# CONNECTOR_BUS.net
KiCad netlist of a schematic drawn in Altium Designer
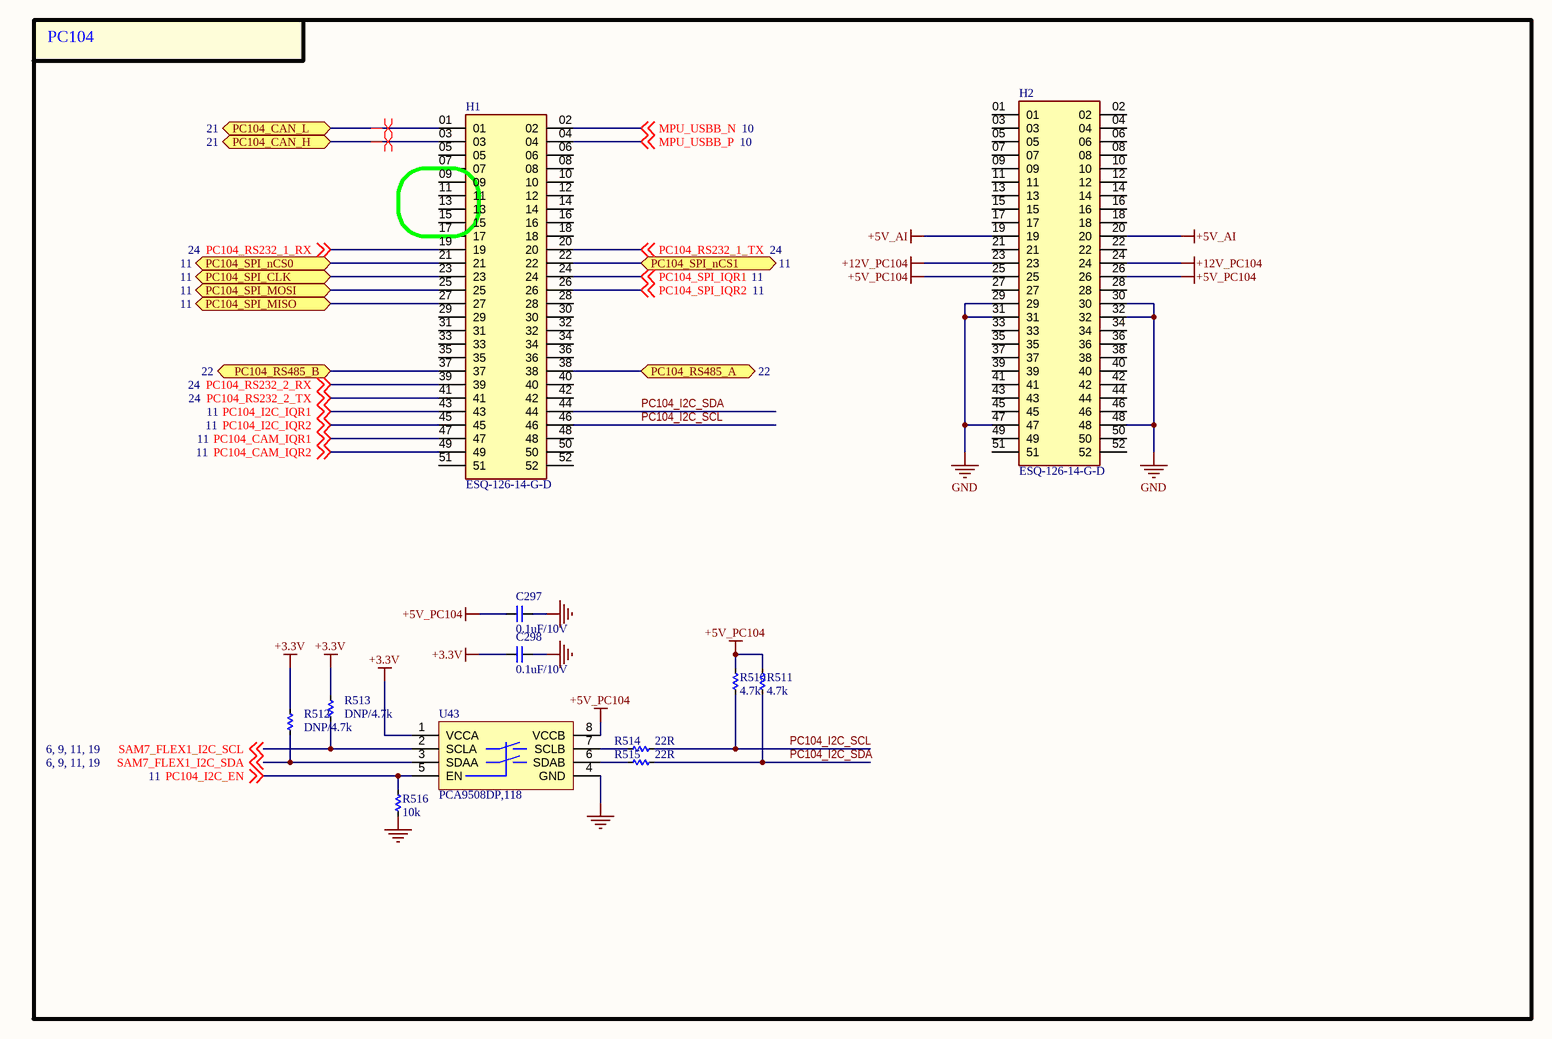
[diagram p0: CONNECTOR_BUS.SchDoc]

(export (version "E")
  (design (tool "Eeschema 10.0.6"))
  (components
    (comp (ref "C297")
      (value "0.1uF/10V")
      (footprint "CAP_C_1005X50_L")
      (description "CAP CHIP")
      (libsource (lib "LABLIB") (part "_CAP_C_2"))
    )
    (comp (ref "C298")
      (value "0.1uF/10V")
      (footprint "CAP_C_1005X50_L")
      (description "CAP CHIP")
      (libsource (lib "LABLIB") (part "_CAP_C_2"))
    )
    (comp (ref "H1")
      (value "ESQ-126-14-G-D")
      (footprint "SAMTEC_ESQ-126-14-G-D")
      (description "CONN SOCKET 52POS 0.1 GOLD PCB")
      (fields (field (name "MF") "Samtec"))
      (libsource (lib "IFBschelib") (part "ESQ-126-14-G-D"))
    )
    (comp (ref "H2")
      (value "ESQ-126-14-G-D")
      (footprint "SAMTEC_ESQ-126-14-G-D")
      (description "CONN SOCKET 52POS 0.1 GOLD PCB")
      (fields (field (name "MF") "Samtec"))
      (libsource (lib "IFBschelib") (part "ESQ-126-14-G-D"))
    )
    (comp (ref "R510")
      (value "4.7k")
      (footprint "RES_C_1005X40")
      (description "RES")
      (libsource (lib "LABLIB") (part "_RES_B_2"))
    )
    (comp (ref "R511")
      (value "4.7k")
      (footprint "RES_C_1005X40")
      (description "RES")
      (libsource (lib "LABLIB") (part "_RES_B_2"))
    )
    (comp (ref "R512")
      (value "DNP/4.7k")
      (footprint "RES_C_1005X40")
      (description "RES")
      (libsource (lib "LABLIB") (part "_RES_B_2"))
    )
    (comp (ref "R513")
      (value "DNP/4.7k")
      (footprint "RES_C_1005X40")
      (description "RES")
      (libsource (lib "LABLIB") (part "_RES_B_2"))
    )
    (comp (ref "R514")
      (value "22R")
      (footprint "RES_C_1005X40")
      (description "RES")
      (libsource (lib "LABLIB") (part "_RES_B_2"))
    )
    (comp (ref "R515")
      (value "22R")
      (footprint "RES_C_1005X40")
      (description "RES")
      (libsource (lib "LABLIB") (part "_RES_B_2"))
    )
    (comp (ref "R516")
      (value "10k")
      (footprint "RES_C_1005X40")
      (description "RES")
      (libsource (lib "LABLIB") (part "_RES_B_2"))
    )
    (comp (ref "U43")
      (value "PCA9508DP,118")
      (footprint "TSOP8")
      (libsource (lib "EXP_HW_V3") (part "PCA9508DP,118"))
    )
  )
  (nets
    (net (code "1") (name "+3.3V") (class "Default")
      (node (ref "C298") (pin "2") (pinfunction "2_2") (pintype "passive"))
      (node (ref "R512") (pin "1") (pinfunction "1_1") (pintype "passive"))
      (node (ref "R513") (pin "1") (pinfunction "1_1") (pintype "passive"))
      (node (ref "U43") (pin "1") (pinfunction "VCCA_1") (pintype "passive"))
    )
    (net (code "2") (name "+5V_AI") (class "Default")
      (node (ref "H2") (pin "19") (pinfunction "19_19") (pintype "passive"))
      (node (ref "H2") (pin "20") (pinfunction "20_20") (pintype "passive"))
    )
    (net (code "3") (name "+5V_PC104") (class "Default")
      (node (ref "C297") (pin "2") (pinfunction "2_2") (pintype "passive"))
      (node (ref "H2") (pin "25") (pinfunction "25_25") (pintype "passive"))
      (node (ref "H2") (pin "26") (pinfunction "26_26") (pintype "passive"))
      (node (ref "R510") (pin "1") (pinfunction "1_1") (pintype "passive"))
      (node (ref "R511") (pin "1") (pinfunction "1_1") (pintype "passive"))
      (node (ref "U43") (pin "8") (pinfunction "VCCB_8") (pintype "passive"))
    )
    (net (code "4") (name "+12V_PC104") (class "Default")
      (node (ref "H2") (pin "23") (pinfunction "23_23") (pintype "passive"))
      (node (ref "H2") (pin "24") (pinfunction "24_24") (pintype "passive"))
    )
    (net (code "5") (name "/PC104_CAN_H") (class "Default")
      (node (ref "H1") (pin "03") (pinfunction "03_03") (pintype "passive"))
    )
    (net (code "6") (name "/PC104_CAN_L") (class "Default")
      (node (ref "H1") (pin "01") (pinfunction "01_01") (pintype "passive"))
    )
    (net (code "7") (name "/PC104_I2C_SCL") (class "Default")
      (node (ref "H1") (pin "46") (pinfunction "46_46") (pintype "passive"))
      (node (ref "R510") (pin "2") (pinfunction "2_2") (pintype "passive"))
      (node (ref "R514") (pin "2") (pinfunction "2_2") (pintype "passive"))
    )
    (net (code "8") (name "/PC104_I2C_SDA") (class "Default")
      (node (ref "H1") (pin "44") (pinfunction "44_44") (pintype "passive"))
      (node (ref "R511") (pin "2") (pinfunction "2_2") (pintype "passive"))
      (node (ref "R515") (pin "2") (pinfunction "2_2") (pintype "passive"))
    )
    (net (code "9") (name "/PC104_RS485_A") (class "Default")
      (node (ref "H1") (pin "38") (pinfunction "38_38") (pintype "passive"))
    )
    (net (code "10") (name "/PC104_RS485_B") (class "Default")
      (node (ref "H1") (pin "37") (pinfunction "37_37") (pintype "passive"))
    )
    (net (code "11") (name "/PC104_SPI_CLK") (class "Default")
      (node (ref "H1") (pin "23") (pinfunction "23_23") (pintype "passive"))
    )
    (net (code "12") (name "/PC104_SPI_MISO") (class "Default")
      (node (ref "H1") (pin "27") (pinfunction "27_27") (pintype "passive"))
    )
    (net (code "13") (name "/PC104_SPI_MOSI") (class "Default")
      (node (ref "H1") (pin "25") (pinfunction "25_25") (pintype "passive"))
    )
    (net (code "14") (name "/PC104_SPI_nCS0") (class "Default")
      (node (ref "H1") (pin "21") (pinfunction "21_21") (pintype "passive"))
    )
    (net (code "15") (name "/PC104_SPI_nCS1") (class "Default")
      (node (ref "H1") (pin "22") (pinfunction "22_22") (pintype "passive"))
    )
    (net (code "16") (name "GND") (class "Default")
      (node (ref "C297") (pin "1") (pinfunction "1_1") (pintype "passive"))
      (node (ref "C298") (pin "1") (pinfunction "1_1") (pintype "passive"))
      (node (ref "H2") (pin "29") (pinfunction "29_29") (pintype "passive"))
      (node (ref "H2") (pin "30") (pinfunction "30_30") (pintype "passive"))
      (node (ref "H2") (pin "31") (pinfunction "31_31") (pintype "passive"))
      (node (ref "H2") (pin "32") (pinfunction "32_32") (pintype "passive"))
      (node (ref "H2") (pin "47") (pinfunction "47_47") (pintype "passive"))
      (node (ref "H2") (pin "48") (pinfunction "48_48") (pintype "passive"))
      (node (ref "R516") (pin "2") (pinfunction "2_2") (pintype "passive"))
      (node (ref "U43") (pin "4") (pinfunction "GND_4") (pintype "passive"))
    )
    (net (code "17") (name "MPU_USBB_N") (class "Default")
      (node (ref "H1") (pin "02") (pinfunction "02_02") (pintype "passive"))
    )
    (net (code "18") (name "MPU_USBB_P") (class "Default")
      (node (ref "H1") (pin "04") (pinfunction "04_04") (pintype "passive"))
    )
    (net (code "19") (name "Net-(U43-SCLB)") (class "Default")
      (node (ref "R514") (pin "1") (pinfunction "1_1") (pintype "passive"))
      (node (ref "U43") (pin "7") (pinfunction "SCLB_7") (pintype "passive"))
    )
    (net (code "20") (name "Net-(U43-SDAB)") (class "Default")
      (node (ref "R515") (pin "1") (pinfunction "1_1") (pintype "passive"))
      (node (ref "U43") (pin "6") (pinfunction "SDAB_6") (pintype "passive"))
    )
    (net (code "21") (name "PC104_CAM_IQR1") (class "Default")
      (node (ref "H1") (pin "47") (pinfunction "47_47") (pintype "passive"))
    )
    (net (code "22") (name "PC104_CAM_IQR2") (class "Default")
      (node (ref "H1") (pin "49") (pinfunction "49_49") (pintype "passive"))
    )
    (net (code "23") (name "PC104_I2C_EN") (class "Default")
      (node (ref "R516") (pin "1") (pinfunction "1_1") (pintype "passive"))
      (node (ref "U43") (pin "5") (pinfunction "EN_5") (pintype "passive"))
    )
    (net (code "24") (name "PC104_I2C_IQR1") (class "Default")
      (node (ref "H1") (pin "43") (pinfunction "43_43") (pintype "passive"))
    )
    (net (code "25") (name "PC104_I2C_IQR2") (class "Default")
      (node (ref "H1") (pin "45") (pinfunction "45_45") (pintype "passive"))
    )
    (net (code "26") (name "PC104_RS232_1_RX") (class "Default")
      (node (ref "H1") (pin "19") (pinfunction "19_19") (pintype "passive"))
    )
    (net (code "27") (name "PC104_RS232_1_TX") (class "Default")
      (node (ref "H1") (pin "20") (pinfunction "20_20") (pintype "passive"))
    )
    (net (code "28") (name "PC104_RS232_2_RX") (class "Default")
      (node (ref "H1") (pin "39") (pinfunction "39_39") (pintype "passive"))
    )
    (net (code "29") (name "PC104_RS232_2_TX") (class "Default")
      (node (ref "H1") (pin "41") (pinfunction "41_41") (pintype "passive"))
    )
    (net (code "30") (name "PC104_SPI_IQR1") (class "Default")
      (node (ref "H1") (pin "24") (pinfunction "24_24") (pintype "passive"))
    )
    (net (code "31") (name "PC104_SPI_IQR2") (class "Default")
      (node (ref "H1") (pin "26") (pinfunction "26_26") (pintype "passive"))
    )
    (net (code "32") (name "SAM7_FLEX1_I2C_SCL") (class "Default")
      (node (ref "R513") (pin "2") (pinfunction "2_2") (pintype "passive"))
      (node (ref "U43") (pin "2") (pinfunction "SCLA_2") (pintype "passive"))
    )
    (net (code "33") (name "SAM7_FLEX1_I2C_SDA") (class "Default")
      (node (ref "R512") (pin "2") (pinfunction "2_2") (pintype "passive"))
      (node (ref "U43") (pin "3") (pinfunction "SDAA_3") (pintype "passive"))
    )
    (net (code "34") (name "unconnected-(H1-Pad05)") (class "Default")
      (node (ref "H1") (pin "05") (pinfunction "05_05") (pintype "passive"))
    )
    (net (code "35") (name "unconnected-(H1-Pad06)") (class "Default")
      (node (ref "H1") (pin "06") (pinfunction "06_06") (pintype "passive"))
    )
    (net (code "36") (name "unconnected-(H1-Pad07)") (class "Default")
      (node (ref "H1") (pin "07") (pinfunction "07_07") (pintype "passive"))
    )
    (net (code "37") (name "unconnected-(H1-Pad08)") (class "Default")
      (node (ref "H1") (pin "08") (pinfunction "08_08") (pintype "passive"))
    )
    (net (code "38") (name "unconnected-(H1-Pad09)") (class "Default")
      (node (ref "H1") (pin "09") (pinfunction "09_09") (pintype "passive"))
    )
    (net (code "39") (name "unconnected-(H1-Pad10)") (class "Default")
      (node (ref "H1") (pin "10") (pinfunction "10_10") (pintype "passive"))
    )
    (net (code "40") (name "unconnected-(H1-Pad11)") (class "Default")
      (node (ref "H1") (pin "11") (pinfunction "11_11") (pintype "passive"))
    )
    (net (code "41") (name "unconnected-(H1-Pad12)") (class "Default")
      (node (ref "H1") (pin "12") (pinfunction "12_12") (pintype "passive"))
    )
    (net (code "42") (name "unconnected-(H1-Pad13)") (class "Default")
      (node (ref "H1") (pin "13") (pinfunction "13_13") (pintype "passive"))
    )
    (net (code "43") (name "unconnected-(H1-Pad14)") (class "Default")
      (node (ref "H1") (pin "14") (pinfunction "14_14") (pintype "passive"))
    )
    (net (code "44") (name "unconnected-(H1-Pad15)") (class "Default")
      (node (ref "H1") (pin "15") (pinfunction "15_15") (pintype "passive"))
    )
    (net (code "45") (name "unconnected-(H1-Pad16)") (class "Default")
      (node (ref "H1") (pin "16") (pinfunction "16_16") (pintype "passive"))
    )
    (net (code "46") (name "unconnected-(H1-Pad17)") (class "Default")
      (node (ref "H1") (pin "17") (pinfunction "17_17") (pintype "passive"))
    )
    (net (code "47") (name "unconnected-(H1-Pad18)") (class "Default")
      (node (ref "H1") (pin "18") (pinfunction "18_18") (pintype "passive"))
    )
    (net (code "48") (name "unconnected-(H1-Pad28)") (class "Default")
      (node (ref "H1") (pin "28") (pinfunction "28_28") (pintype "passive"))
    )
    (net (code "49") (name "unconnected-(H1-Pad29)") (class "Default")
      (node (ref "H1") (pin "29") (pinfunction "29_29") (pintype "passive"))
    )
    (net (code "50") (name "unconnected-(H1-Pad30)") (class "Default")
      (node (ref "H1") (pin "30") (pinfunction "30_30") (pintype "passive"))
    )
    (net (code "51") (name "unconnected-(H1-Pad31)") (class "Default")
      (node (ref "H1") (pin "31") (pinfunction "31_31") (pintype "passive"))
    )
    (net (code "52") (name "unconnected-(H1-Pad32)") (class "Default")
      (node (ref "H1") (pin "32") (pinfunction "32_32") (pintype "passive"))
    )
    (net (code "53") (name "unconnected-(H1-Pad33)") (class "Default")
      (node (ref "H1") (pin "33") (pinfunction "33_33") (pintype "passive"))
    )
    (net (code "54") (name "unconnected-(H1-Pad34)") (class "Default")
      (node (ref "H1") (pin "34") (pinfunction "34_34") (pintype "passive"))
    )
    (net (code "55") (name "unconnected-(H1-Pad35)") (class "Default")
      (node (ref "H1") (pin "35") (pinfunction "35_35") (pintype "passive"))
    )
    (net (code "56") (name "unconnected-(H1-Pad36)") (class "Default")
      (node (ref "H1") (pin "36") (pinfunction "36_36") (pintype "passive"))
    )
    (net (code "57") (name "unconnected-(H1-Pad40)") (class "Default")
      (node (ref "H1") (pin "40") (pinfunction "40_40") (pintype "passive"))
    )
    (net (code "58") (name "unconnected-(H1-Pad42)") (class "Default")
      (node (ref "H1") (pin "42") (pinfunction "42_42") (pintype "passive"))
    )
    (net (code "59") (name "unconnected-(H1-Pad48)") (class "Default")
      (node (ref "H1") (pin "48") (pinfunction "48_48") (pintype "passive"))
    )
    (net (code "60") (name "unconnected-(H1-Pad50)") (class "Default")
      (node (ref "H1") (pin "50") (pinfunction "50_50") (pintype "passive"))
    )
    (net (code "61") (name "unconnected-(H1-Pad51)") (class "Default")
      (node (ref "H1") (pin "51") (pinfunction "51_51") (pintype "passive"))
    )
    (net (code "62") (name "unconnected-(H1-Pad52)") (class "Default")
      (node (ref "H1") (pin "52") (pinfunction "52_52") (pintype "passive"))
    )
    (net (code "63") (name "unconnected-(H2-Pad01)") (class "Default")
      (node (ref "H2") (pin "01") (pinfunction "01_01") (pintype "passive"))
    )
    (net (code "64") (name "unconnected-(H2-Pad02)") (class "Default")
      (node (ref "H2") (pin "02") (pinfunction "02_02") (pintype "passive"))
    )
    (net (code "65") (name "unconnected-(H2-Pad03)") (class "Default")
      (node (ref "H2") (pin "03") (pinfunction "03_03") (pintype "passive"))
    )
    (net (code "66") (name "unconnected-(H2-Pad04)") (class "Default")
      (node (ref "H2") (pin "04") (pinfunction "04_04") (pintype "passive"))
    )
    (net (code "67") (name "unconnected-(H2-Pad05)") (class "Default")
      (node (ref "H2") (pin "05") (pinfunction "05_05") (pintype "passive"))
    )
    (net (code "68") (name "unconnected-(H2-Pad06)") (class "Default")
      (node (ref "H2") (pin "06") (pinfunction "06_06") (pintype "passive"))
    )
    (net (code "69") (name "unconnected-(H2-Pad07)") (class "Default")
      (node (ref "H2") (pin "07") (pinfunction "07_07") (pintype "passive"))
    )
    (net (code "70") (name "unconnected-(H2-Pad08)") (class "Default")
      (node (ref "H2") (pin "08") (pinfunction "08_08") (pintype "passive"))
    )
    (net (code "71") (name "unconnected-(H2-Pad09)") (class "Default")
      (node (ref "H2") (pin "09") (pinfunction "09_09") (pintype "passive"))
    )
    (net (code "72") (name "unconnected-(H2-Pad10)") (class "Default")
      (node (ref "H2") (pin "10") (pinfunction "10_10") (pintype "passive"))
    )
    (net (code "73") (name "unconnected-(H2-Pad11)") (class "Default")
      (node (ref "H2") (pin "11") (pinfunction "11_11") (pintype "passive"))
    )
    (net (code "74") (name "unconnected-(H2-Pad12)") (class "Default")
      (node (ref "H2") (pin "12") (pinfunction "12_12") (pintype "passive"))
    )
    (net (code "75") (name "unconnected-(H2-Pad13)") (class "Default")
      (node (ref "H2") (pin "13") (pinfunction "13_13") (pintype "passive"))
    )
    (net (code "76") (name "unconnected-(H2-Pad14)") (class "Default")
      (node (ref "H2") (pin "14") (pinfunction "14_14") (pintype "passive"))
    )
    (net (code "77") (name "unconnected-(H2-Pad15)") (class "Default")
      (node (ref "H2") (pin "15") (pinfunction "15_15") (pintype "passive"))
    )
    (net (code "78") (name "unconnected-(H2-Pad16)") (class "Default")
      (node (ref "H2") (pin "16") (pinfunction "16_16") (pintype "passive"))
    )
    (net (code "79") (name "unconnected-(H2-Pad17)") (class "Default")
      (node (ref "H2") (pin "17") (pinfunction "17_17") (pintype "passive"))
    )
    (net (code "80") (name "unconnected-(H2-Pad18)") (class "Default")
      (node (ref "H2") (pin "18") (pinfunction "18_18") (pintype "passive"))
    )
    (net (code "81") (name "unconnected-(H2-Pad21)") (class "Default")
      (node (ref "H2") (pin "21") (pinfunction "21_21") (pintype "passive"))
    )
    (net (code "82") (name "unconnected-(H2-Pad22)") (class "Default")
      (node (ref "H2") (pin "22") (pinfunction "22_22") (pintype "passive"))
    )
    (net (code "83") (name "unconnected-(H2-Pad27)") (class "Default")
      (node (ref "H2") (pin "27") (pinfunction "27_27") (pintype "passive"))
    )
    (net (code "84") (name "unconnected-(H2-Pad28)") (class "Default")
      (node (ref "H2") (pin "28") (pinfunction "28_28") (pintype "passive"))
    )
    (net (code "85") (name "unconnected-(H2-Pad33)") (class "Default")
      (node (ref "H2") (pin "33") (pinfunction "33_33") (pintype "passive"))
    )
    (net (code "86") (name "unconnected-(H2-Pad34)") (class "Default")
      (node (ref "H2") (pin "34") (pinfunction "34_34") (pintype "passive"))
    )
    (net (code "87") (name "unconnected-(H2-Pad35)") (class "Default")
      (node (ref "H2") (pin "35") (pinfunction "35_35") (pintype "passive"))
    )
    (net (code "88") (name "unconnected-(H2-Pad36)") (class "Default")
      (node (ref "H2") (pin "36") (pinfunction "36_36") (pintype "passive"))
    )
    (net (code "89") (name "unconnected-(H2-Pad37)") (class "Default")
      (node (ref "H2") (pin "37") (pinfunction "37_37") (pintype "passive"))
    )
    (net (code "90") (name "unconnected-(H2-Pad38)") (class "Default")
      (node (ref "H2") (pin "38") (pinfunction "38_38") (pintype "passive"))
    )
    (net (code "91") (name "unconnected-(H2-Pad39)") (class "Default")
      (node (ref "H2") (pin "39") (pinfunction "39_39") (pintype "passive"))
    )
    (net (code "92") (name "unconnected-(H2-Pad40)") (class "Default")
      (node (ref "H2") (pin "40") (pinfunction "40_40") (pintype "passive"))
    )
    (net (code "93") (name "unconnected-(H2-Pad41)") (class "Default")
      (node (ref "H2") (pin "41") (pinfunction "41_41") (pintype "passive"))
    )
    (net (code "94") (name "unconnected-(H2-Pad42)") (class "Default")
      (node (ref "H2") (pin "42") (pinfunction "42_42") (pintype "passive"))
    )
    (net (code "95") (name "unconnected-(H2-Pad43)") (class "Default")
      (node (ref "H2") (pin "43") (pinfunction "43_43") (pintype "passive"))
    )
    (net (code "96") (name "unconnected-(H2-Pad44)") (class "Default")
      (node (ref "H2") (pin "44") (pinfunction "44_44") (pintype "passive"))
    )
    (net (code "97") (name "unconnected-(H2-Pad45)") (class "Default")
      (node (ref "H2") (pin "45") (pinfunction "45_45") (pintype "passive"))
    )
    (net (code "98") (name "unconnected-(H2-Pad46)") (class "Default")
      (node (ref "H2") (pin "46") (pinfunction "46_46") (pintype "passive"))
    )
    (net (code "99") (name "unconnected-(H2-Pad49)") (class "Default")
      (node (ref "H2") (pin "49") (pinfunction "49_49") (pintype "passive"))
    )
    (net (code "100") (name "unconnected-(H2-Pad50)") (class "Default")
      (node (ref "H2") (pin "50") (pinfunction "50_50") (pintype "passive"))
    )
    (net (code "101") (name "unconnected-(H2-Pad51)") (class "Default")
      (node (ref "H2") (pin "51") (pinfunction "51_51") (pintype "passive"))
    )
    (net (code "102") (name "unconnected-(H2-Pad52)") (class "Default")
      (node (ref "H2") (pin "52") (pinfunction "52_52") (pintype "passive"))
    )
  )
)
